# INVERTER_12V_TO_220V_FROM_ATX_POWER_SUPP.net
KiCad netlist of a schematic drawn in Altium Designer
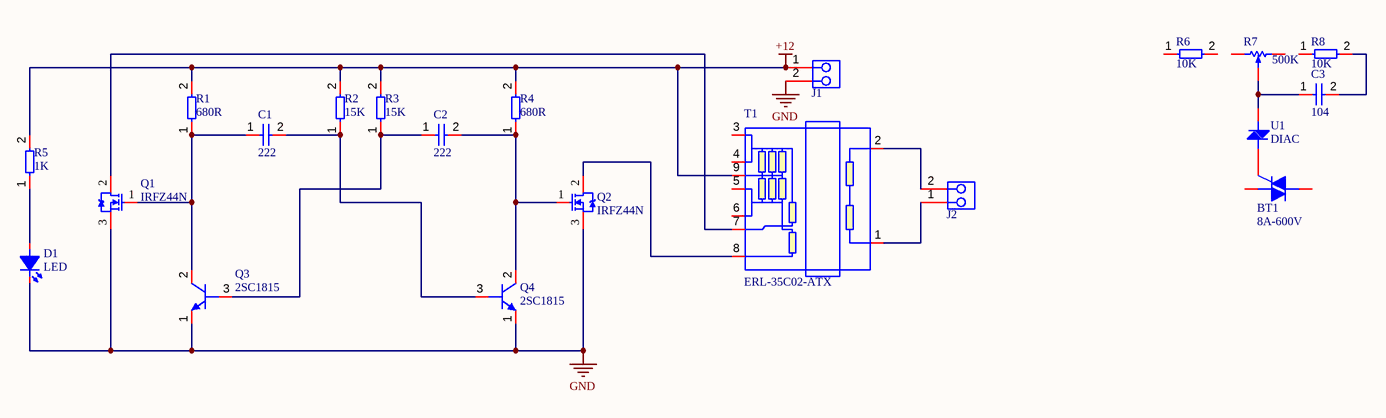
[diagram p0: INVERTER_12V_TO_220V_FROM_ATX_POWER_SUPPLY.SchDoc]

(export (version "E")
  (design (tool "Eeschema 10.0.6"))
  (components
    (comp (ref "BT1") (value "8A-600V") (footprint "TO-220A") (libsource (lib "Lib31082020") (part "BT137")))
    (comp (ref "C1")
      (value "222")
      (footprint "CAP_Ceramic_Disc_3")
      (libsource (lib "Lib31082020") (part "Capacitors(Disc)"))
    )
    (comp (ref "C2")
      (value "222")
      (footprint "CAP_Ceramic_Disc_3")
      (libsource (lib "Lib31082020") (part "Capacitors(Disc)"))
    )
    (comp (ref "C3")
      (value "104")
      (footprint "CAP_Ceramic_Disc_2")
      (libsource (lib "Lib31082020") (part "Capacitors(Disc)"))
    )
    (comp (ref "D1") (value "LED") (footprint "LED_5MM") (libsource (lib "Lib31082020") (part "LED 5MM")))
    (comp (ref "J1")
      (value "DEGSON")
      (footprint "DG127-5.0-02P-14-00AH")
      (libsource (lib "") (part "DG127-5.0-02P-14-00AH_1"))
    )
    (comp (ref "J2")
      (value "DEGSON")
      (footprint "DG127-5.0-02P-14-00AH")
      (libsource (lib "Lib31082020") (part "DG127-5.0-02P-14-00AH"))
    )
    (comp (ref "Q1") (value "IRFZ44N") (footprint "TO-220A") (libsource (lib "Lib31082020") (part "IRFZ44N")))
    (comp (ref "Q2") (value "IRFZ44N") (footprint "TO-220A") (libsource (lib "Lib31082020") (part "IRFZ44N")))
    (comp (ref "Q3")
      (value "2SC1815")
      (footprint "TO-92")
      (libsource (lib "Lib31082020") (part "2SC1815 (TO-92)"))
    )
    (comp (ref "Q4")
      (value "2SC1815")
      (footprint "TO-92")
      (libsource (lib "Lib31082020") (part "2SC1815 (TO-92)"))
    )
    (comp (ref "R1")
      (value "680R")
      (footprint "RES-0.25W-H-MF")
      (libsource (lib "Lib31082020") (part "Resistors THD"))
    )
    (comp (ref "R2")
      (value "15K")
      (footprint "RES-0.25W-H-MF")
      (libsource (lib "Lib31082020") (part "Resistors THD"))
    )
    (comp (ref "R3")
      (value "15K")
      (footprint "RES-0.25W-H-MF")
      (libsource (lib "Lib31082020") (part "Resistors THD"))
    )
    (comp (ref "R4")
      (value "680R")
      (footprint "RES-0.25W-H-MF")
      (libsource (lib "Lib31082020") (part "Resistors THD"))
    )
    (comp (ref "R5")
      (value "1K")
      (footprint "RES-0.25W-H-MF")
      (libsource (lib "Lib31082020") (part "Resistors THD"))
    )
    (comp (ref "R6") (value "10K") (footprint "RES-0.25W-H-MF") (libsource (lib "") (part "Resistors THD_1")))
    (comp (ref "R7")
      (value "500K")
      (footprint "TrimmingPotentiometer")
      (description "Bourns 3296 pot")
      (libsource (lib "Lib31082020") (part "Res-Var"))
    )
    (comp (ref "R8") (value "10K") (footprint "RES-0.25W-H-MF") (libsource (lib "") (part "Resistors THD_1")))
    (comp (ref "T1")
      (value "ERL-35C02-ATX")
      (footprint "TRANSFORMER-ERL-35C02-ATX")
      (libsource (lib "Lib31082020") (part "TRANS-ERL-35C02-ATX"))
    )
    (comp (ref "U1") (value "DIAC") (footprint "SOT23-3") (libsource (lib "Lib31082020") (part "DIAC-DB3")))
  )
  (nets
    (net (code "1") (name "+12") (class "Default")
      (node (ref "J1") (pin "1") (pinfunction "1_1") (pintype "passive"))
      (node (ref "R1") (pin "2") (pinfunction "2_2") (pintype "passive"))
      (node (ref "R2") (pin "2") (pinfunction "2_2") (pintype "passive"))
      (node (ref "R3") (pin "2") (pinfunction "2_2") (pintype "passive"))
      (node (ref "R4") (pin "2") (pinfunction "2_2") (pintype "passive"))
      (node (ref "R5") (pin "2") (pinfunction "2_2") (pintype "passive"))
      (node (ref "T1") (pin "9") (pinfunction "9_9") (pintype "passive"))
    )
    (net (code "2") (name "GND") (class "Default")
      (node (ref "D1") (pin "2") (pinfunction "K_2") (pintype "passive"))
      (node (ref "J1") (pin "2") (pinfunction "2_2") (pintype "passive"))
      (node (ref "Q1") (pin "3") (pinfunction "S_3") (pintype "passive"))
      (node (ref "Q2") (pin "3") (pinfunction "S_3") (pintype "passive"))
      (node (ref "Q3") (pin "1") (pinfunction "E_1") (pintype "passive"))
      (node (ref "Q4") (pin "1") (pinfunction "E_1") (pintype "passive"))
    )
    (net (code "3") (name "Net-(BT1-G)") (class "Default")
      (node (ref "BT1") (pin "3") (pinfunction "G_3") (pintype "passive"))
      (node (ref "U1") (pin "2") (pinfunction "2_2") (pintype "passive"))
    )
    (net (code "4") (name "Net-(C3-Pad2)") (class "Default")
      (node (ref "C3") (pin "2") (pinfunction "2_2") (pintype "passive"))
      (node (ref "R8") (pin "2") (pinfunction "2_2") (pintype "passive"))
    )
    (net (code "5") (name "Net-(D1-A)") (class "Default")
      (node (ref "D1") (pin "1") (pinfunction "A_1") (pintype "passive"))
      (node (ref "R5") (pin "1") (pinfunction "1_1") (pintype "passive"))
    )
    (net (code "6") (name "Net-(J2-Pad1)") (class "Default")
      (node (ref "J2") (pin "1") (pinfunction "1_1") (pintype "passive"))
      (node (ref "T1") (pin "1") (pinfunction "1_1") (pintype "passive"))
    )
    (net (code "7") (name "Net-(J2-Pad2)") (class "Default")
      (node (ref "J2") (pin "2") (pinfunction "2_2") (pintype "passive"))
      (node (ref "T1") (pin "2") (pinfunction "2_2") (pintype "passive"))
    )
    (net (code "8") (name "Net-(Q1-D)") (class "Default")
      (node (ref "Q1") (pin "2") (pinfunction "D_2") (pintype "passive"))
      (node (ref "T1") (pin "7") (pinfunction "7_7") (pintype "passive"))
    )
    (net (code "9") (name "Net-(Q1-G)") (class "Default")
      (node (ref "C1") (pin "1") (pinfunction "1_1") (pintype "passive"))
      (node (ref "Q1") (pin "1") (pinfunction "G_1") (pintype "passive"))
      (node (ref "Q3") (pin "2") (pinfunction "C_2") (pintype "passive"))
      (node (ref "R1") (pin "1") (pinfunction "1_1") (pintype "passive"))
    )
    (net (code "10") (name "Net-(Q2-D)") (class "Default")
      (node (ref "Q2") (pin "2") (pinfunction "D_2") (pintype "passive"))
      (node (ref "T1") (pin "8") (pinfunction "8_8") (pintype "passive"))
    )
    (net (code "11") (name "Net-(Q2-G)") (class "Default")
      (node (ref "C2") (pin "2") (pinfunction "2_2") (pintype "passive"))
      (node (ref "Q2") (pin "1") (pinfunction "G_1") (pintype "passive"))
      (node (ref "Q4") (pin "2") (pinfunction "C_2") (pintype "passive"))
      (node (ref "R4") (pin "1") (pinfunction "1_1") (pintype "passive"))
    )
    (net (code "12") (name "Net-(Q3-B)") (class "Default")
      (node (ref "C2") (pin "1") (pinfunction "1_1") (pintype "passive"))
      (node (ref "Q3") (pin "3") (pinfunction "B_3") (pintype "passive"))
      (node (ref "R3") (pin "1") (pinfunction "1_1") (pintype "passive"))
    )
    (net (code "13") (name "Net-(Q4-B)") (class "Default")
      (node (ref "C1") (pin "2") (pinfunction "2_2") (pintype "passive"))
      (node (ref "Q4") (pin "3") (pinfunction "B_3") (pintype "passive"))
      (node (ref "R2") (pin "1") (pinfunction "1_1") (pintype "passive"))
    )
    (net (code "14") (name "Net-(R7-W)") (class "Default")
      (node (ref "C3") (pin "1") (pinfunction "1_1") (pintype "passive"))
      (node (ref "R7") (pin "2") (pinfunction "W_2") (pintype "passive"))
      (node (ref "U1") (pin "1") (pinfunction "4_1") (pintype "passive"))
    )
    (net (code "15") (name "unconnected-(BT1-T1-Pad1)") (class "Default")
      (node (ref "BT1") (pin "1") (pinfunction "T1_1") (pintype "passive"))
    )
    (net (code "16") (name "unconnected-(BT1-T2-Pad2)") (class "Default")
      (node (ref "BT1") (pin "2") (pinfunction "T2_2") (pintype "passive"))
    )
    (net (code "17") (name "unconnected-(R6-Pad1)") (class "Default")
      (node (ref "R6") (pin "1") (pinfunction "1_1") (pintype "passive"))
    )
    (net (code "18") (name "unconnected-(R6-Pad2)") (class "Default")
      (node (ref "R6") (pin "2") (pinfunction "2_2") (pintype "passive"))
    )
    (net (code "19") (name "unconnected-(R7-+-Pad1)") (class "Default")
      (node (ref "R7") (pin "1") (pinfunction "+_1") (pintype "passive"))
    )
    (net (code "20") (name "unconnected-(R7---Pad3)") (class "Default")
      (node (ref "R7") (pin "3") (pinfunction "-_3") (pintype "passive"))
    )
    (net (code "21") (name "unconnected-(R8-Pad1)") (class "Default")
      (node (ref "R8") (pin "1") (pinfunction "1_1") (pintype "passive"))
    )
    (net (code "22") (name "unconnected-(T1-Pad3)") (class "Default")
      (node (ref "T1") (pin "3") (pinfunction "3_3") (pintype "passive"))
    )
    (net (code "23") (name "unconnected-(T1-Pad4)") (class "Default")
      (node (ref "T1") (pin "4") (pinfunction "4_4") (pintype "passive"))
    )
    (net (code "24") (name "unconnected-(T1-Pad5)") (class "Default")
      (node (ref "T1") (pin "5") (pinfunction "5_5") (pintype "passive"))
    )
    (net (code "25") (name "unconnected-(T1-Pad6)") (class "Default")
      (node (ref "T1") (pin "6") (pinfunction "6_6") (pintype "passive"))
    )
  )
)
